# wifi.net
KiCad netlist of a schematic drawn in Altium Designer
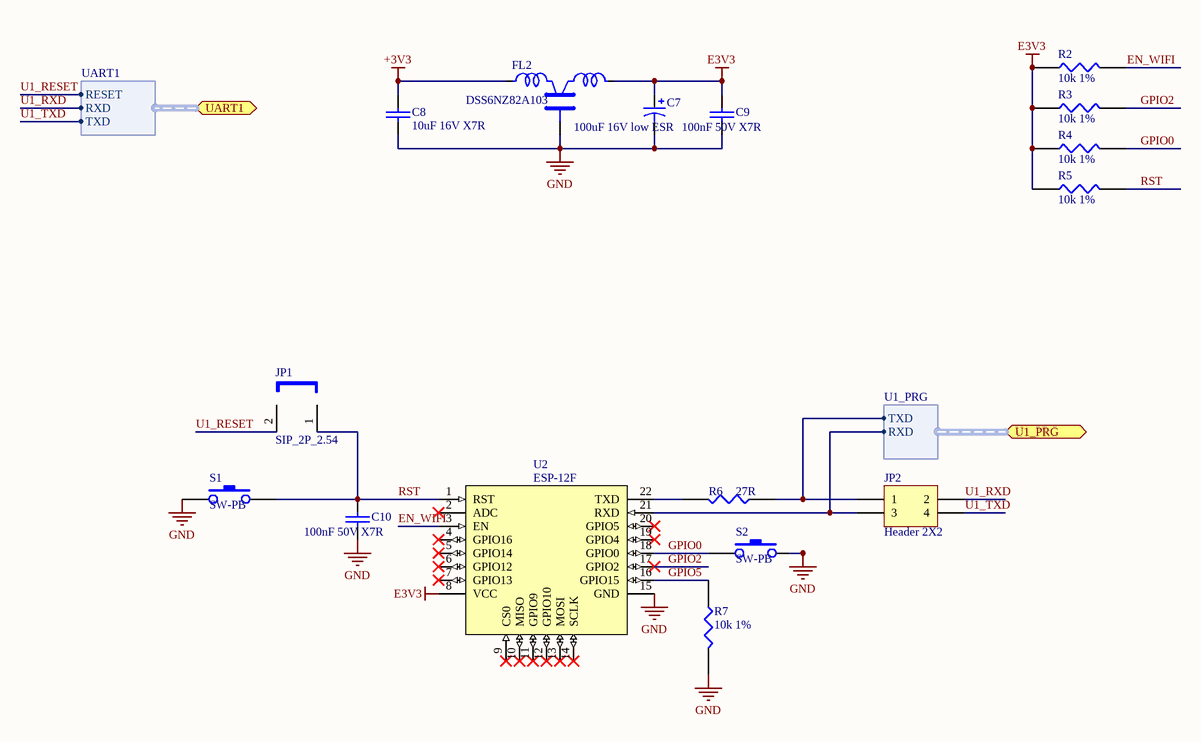
[diagram p0: wifi.SchDoc]

(export (version "E")
  (design (tool "Eeschema 10.0.6"))
  (components
    (comp (ref "C7")
      (value "100uF 16V low ESR")
      (footprint "Capacitor Polar Radial Cylinder:CAPPR2-5x11")
      (description "Polarized Capacitor (Radial)")
      (libsource (lib "Miscellaneous Devices") (part "Cap Pol1"))
    )
    (comp (ref "C8")
      (value "10uF 16V X7R")
      (footprint "IPC-7352 Chip_Capacitor_N:CAPC3216N")
      (libsource (lib "*") (part "CAP"))
    )
    (comp (ref "C9")
      (value "100nF 50V X7R")
      (footprint "IPC-7352 Chip_Capacitor_N:CAPC2012N")
      (libsource (lib "*") (part "CAP"))
    )
    (comp (ref "C10")
      (value "100nF 50V X7R")
      (footprint "IPC-7352 Chip_Capacitor_N:CAPC2012N")
      (libsource (lib "*") (part "CAP"))
    )
    (comp (ref "FL2")
      (value "DSS6NZ82A103")
      (footprint "UserPcbLib:DSS6")
      (description "Murata EMI suppression filter")
      (fields (field (name "MANUFACTURER") "Murata"))
      (libsource (lib "UserSchlib") (part "DSS6"))
    )
    (comp (ref "JP1")
      (value "SIP_2P_2.54")
      (footprint "UserPcbLib:JP2-P2.54")
      (description "Jumper")
      (libsource (lib "*") (part "JUMPER"))
    )
    (comp (ref "JP2")
      (value "Header 2X2")
      (footprint "HDR2X2")
      (description "Header, 2-Pin, Dual row")
      (fields (field (name "PUBLISHER") "Altium Limited"))
      (libsource (lib "Miscellaneous Connectors") (part "Header 2X2"))
    )
    (comp (ref "R2")
      (value "10k 1%")
      (footprint "IPC-7352 Chip_Resistor_N:RESC2012N")
      (libsource (lib "*") (part "RES1"))
    )
    (comp (ref "R3")
      (value "10k 1%")
      (footprint "IPC-7352 Chip_Resistor_N:RESC2012N")
      (libsource (lib "*") (part "RES1"))
    )
    (comp (ref "R4")
      (value "10k 1%")
      (footprint "IPC-7352 Chip_Resistor_N:RESC2012N")
      (libsource (lib "*") (part "RES1"))
    )
    (comp (ref "R5")
      (value "10k 1%")
      (footprint "IPC-7352 Chip_Resistor_N:RESC2012N")
      (libsource (lib "*") (part "RES1"))
    )
    (comp (ref "R6")
      (value "27R")
      (footprint "IPC-7352 Chip_Resistor_N:RESC2012N")
      (libsource (lib "*") (part "RES1"))
    )
    (comp (ref "R7")
      (value "10k 1%")
      (footprint "IPC-7352 Chip_Resistor_N:RESC2012N")
      (libsource (lib "*") (part "RES1"))
    )
    (comp (ref "S1") (value "SW-PB") (footprint "SW5X7") (libsource (lib "*") (part "SW-PB")))
    (comp (ref "S2") (value "SW-PB") (footprint "SW5X7") (libsource (lib "*") (part "SW-PB")))
    (comp (ref "U2")
      (value "ESP-12F")
      (footprint "UserPcbLib:ESP-12F")
      (description "Wi-Fi module")
      (fields (field (name "MANUFACTURER") "Ai-Thinker"))
      (libsource (lib "UserSchlib") (part "ESP-12F"))
    )
  )
  (nets
    (net (code "3") (name "+3V3") (class "Default")
      (node (ref "C8") (pin "1") (pintype "passive"))
      (node (ref "FL2") (pin "1") (pinfunction "1_1") (pintype "power_in"))
    )
    (net (code "4") (name "/EN_WIFI") (class "Default")
      (node (ref "R2") (pin "2") (pinfunction "2_2") (pintype "passive"))
      (node (ref "U2") (pin "3") (pinfunction "EN_3") (pintype "input"))
    )
    (net (code "5") (name "/GPIO0") (class "Default")
      (node (ref "R4") (pin "2") (pinfunction "2_2") (pintype "passive"))
      (node (ref "S2") (pin "1") (pinfunction "1_1") (pintype "passive"))
      (node (ref "U2") (pin "18") (pinfunction "GPIO0_18") (pintype "bidirectional"))
    )
    (net (code "6") (name "/GPIO2") (class "Default")
      (node (ref "R3") (pin "2") (pinfunction "2_2") (pintype "passive"))
      (node (ref "U2") (pin "17") (pinfunction "GPIO2_17") (pintype "bidirectional"))
    )
    (net (code "7") (name "/GPIO5") (class "Default")
      (node (ref "R7") (pin "1") (pinfunction "1_1") (pintype "passive"))
      (node (ref "U2") (pin "16") (pinfunction "GPIO15_16") (pintype "bidirectional"))
    )
    (net (code "8") (name "/RST") (class "Default")
      (node (ref "C10") (pin "1") (pintype "passive"))
      (node (ref "JP1") (pin "1") (pinfunction "1_1") (pintype "passive"))
      (node (ref "R5") (pin "2") (pinfunction "2_2") (pintype "passive"))
      (node (ref "S1") (pin "2") (pinfunction "2_2") (pintype "passive"))
      (node (ref "U2") (pin "1") (pinfunction "RST_1") (pintype "input"))
    )
    (net (code "9") (name "/U1_RESET") (class "Default")
      (node (ref "JP1") (pin "2") (pinfunction "2_2") (pintype "passive"))
    )
    (net (code "10") (name "/U1_RXD") (class "Default")
      (node (ref "JP2") (pin "2") (pinfunction "2_2") (pintype "passive"))
    )
    (net (code "11") (name "/U1_TXD") (class "Default")
      (node (ref "JP2") (pin "4") (pinfunction "4_4") (pintype "passive"))
    )
    (net (code "14") (name "E3V3") (class "Default")
      (node (ref "C7") (pin "1") (pinfunction "1_1") (pintype "passive"))
      (node (ref "C9") (pin "1") (pintype "passive"))
      (node (ref "FL2") (pin "3") (pinfunction "3_3") (pintype "power_in"))
      (node (ref "R2") (pin "1") (pinfunction "1_1") (pintype "passive"))
      (node (ref "R3") (pin "1") (pinfunction "1_1") (pintype "passive"))
      (node (ref "R4") (pin "1") (pinfunction "1_1") (pintype "passive"))
      (node (ref "R5") (pin "1") (pinfunction "1_1") (pintype "passive"))
      (node (ref "U2") (pin "8") (pinfunction "VCC_8") (pintype "power_in"))
    )
    (net (code "15") (name "GND") (class "Default")
      (node (ref "C10") (pin "2") (pintype "passive"))
      (node (ref "C7") (pin "2") (pinfunction "2_2") (pintype "passive"))
      (node (ref "C8") (pin "2") (pintype "passive"))
      (node (ref "C9") (pin "2") (pintype "passive"))
      (node (ref "FL2") (pin "2") (pinfunction "2_2") (pintype "power_in"))
      (node (ref "R7") (pin "2") (pinfunction "2_2") (pintype "passive"))
      (node (ref "S1") (pin "1") (pinfunction "1_1") (pintype "passive"))
      (node (ref "S2") (pin "2") (pinfunction "2_2") (pintype "passive"))
      (node (ref "U2") (pin "15") (pinfunction "GND_15") (pintype "power_in"))
    )
    (net (code "16") (name "Net-(JP2-Pad1)") (class "Default")
      (node (ref "JP2") (pin "1") (pinfunction "1_1") (pintype "passive"))
      (node (ref "R6") (pin "1") (pinfunction "1_1") (pintype "passive"))
    )
    (net (code "17") (name "Net-(U2-RXD)") (class "Default")
      (node (ref "JP2") (pin "3") (pinfunction "3_3") (pintype "passive"))
      (node (ref "U2") (pin "21") (pinfunction "RXD_21") (pintype "input"))
    )
    (net (code "18") (name "Net-(U2-TXD)") (class "Default")
      (node (ref "R6") (pin "2") (pinfunction "2_2") (pintype "passive"))
      (node (ref "U2") (pin "22") (pinfunction "TXD_22") (pintype "tri_state"))
    )
    (net (code "19") (name "unconnected-(U2-ADC-Pad2)") (class "Default")
      (node (ref "U2") (pin "2") (pinfunction "ADC_2") (pintype "passive+no_connect"))
    )
    (net (code "20") (name "unconnected-(U2-CS0-Pad9)") (class "Default")
      (node (ref "U2") (pin "9") (pinfunction "CS0_9") (pintype "input+no_connect"))
    )
    (net (code "21") (name "unconnected-(U2-GPIO4-Pad19)") (class "Default")
      (node (ref "U2") (pin "19") (pinfunction "GPIO4_19") (pintype "bidirectional+no_connect"))
    )
    (net (code "22") (name "unconnected-(U2-GPIO5-Pad20)") (class "Default")
      (node (ref "U2") (pin "20") (pinfunction "GPIO5_20") (pintype "bidirectional+no_connect"))
    )
    (net (code "23") (name "unconnected-(U2-GPIO9-Pad11)") (class "Default")
      (node (ref "U2") (pin "11") (pinfunction "GPIO9_11") (pintype "bidirectional+no_connect"))
    )
    (net (code "24") (name "unconnected-(U2-GPIO10-Pad12)") (class "Default")
      (node (ref "U2") (pin "12") (pinfunction "GPIO10_12") (pintype "bidirectional+no_connect"))
    )
    (net (code "25") (name "unconnected-(U2-GPIO12-Pad6)") (class "Default")
      (node (ref "U2") (pin "6") (pinfunction "GPIO12_6") (pintype "bidirectional+no_connect"))
    )
    (net (code "26") (name "unconnected-(U2-GPIO13-Pad7)") (class "Default")
      (node (ref "U2") (pin "7") (pinfunction "GPIO13_7") (pintype "bidirectional+no_connect"))
    )
    (net (code "27") (name "unconnected-(U2-GPIO14-Pad5)") (class "Default")
      (node (ref "U2") (pin "5") (pinfunction "GPIO14_5") (pintype "bidirectional+no_connect"))
    )
    (net (code "28") (name "unconnected-(U2-GPIO16-Pad4)") (class "Default")
      (node (ref "U2") (pin "4") (pinfunction "GPIO16_4") (pintype "bidirectional+no_connect"))
    )
    (net (code "29") (name "unconnected-(U2-MISO-Pad10)") (class "Default")
      (node (ref "U2") (pin "10") (pinfunction "MISO_10") (pintype "bidirectional+no_connect"))
    )
    (net (code "30") (name "unconnected-(U2-MOSI-Pad13)") (class "Default")
      (node (ref "U2") (pin "13") (pinfunction "MOSI_13") (pintype "bidirectional+no_connect"))
    )
    (net (code "31") (name "unconnected-(U2-SCLK-Pad14)") (class "Default")
      (node (ref "U2") (pin "14") (pinfunction "SCLK_14") (pintype "bidirectional+no_connect"))
    )
  )
)
